# meuRelogio.net
KiCad netlist of a schematic drawn in EAGLE
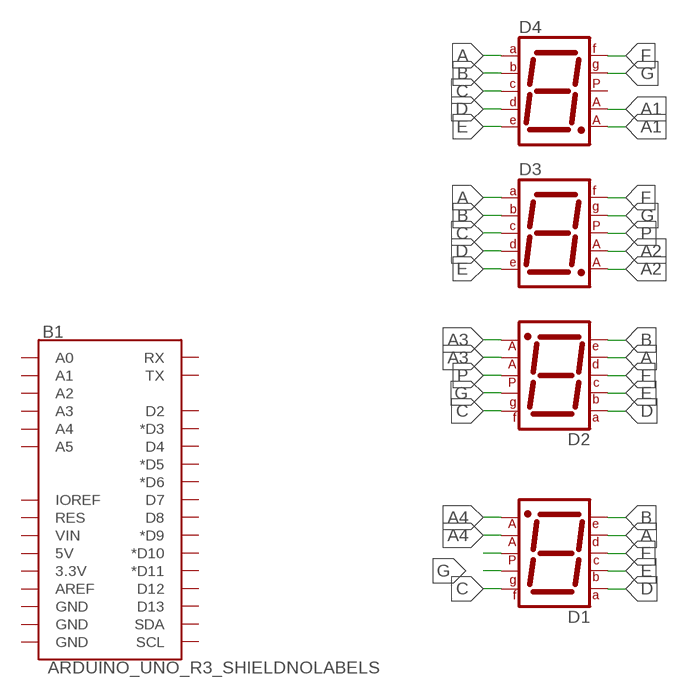
[diagram p0: schematic, sheet 1]

(export (version "E")
  (design (tool "Eeschema 10.0.6"))
  (components
    (comp (ref "B1")
      (value "ARDUINO_UNO_R3_SHIELDNOLABELS")
      (footprint "eagle-import:UNO_R3_SHIELD_NOLABELS")
      (libsource (lib "eagle-import") (part "ARDUINO_UNO_R3_SHIELDNOLABELS"))
    )
    (comp (ref "D1")
      (value "7SEG-CA")
      (footprint "eagle-import:7SEG-13")
      (libsource (lib "eagle-import") (part "7SEG-CA"))
    )
    (comp (ref "D2")
      (value "7SEG-CA")
      (footprint "eagle-import:7SEG-13")
      (libsource (lib "eagle-import") (part "7SEG-CA"))
    )
    (comp (ref "D3")
      (value "7SEG-CA")
      (footprint "eagle-import:7SEG-13")
      (libsource (lib "eagle-import") (part "7SEG-CA"))
    )
    (comp (ref "D4")
      (value "7SEG-CA")
      (footprint "eagle-import:7SEG-13")
      (libsource (lib "eagle-import") (part "7SEG-CA"))
    )
  )
  (nets
    (net (code "1") (name "A") (class "Default")
      (node (ref "D1") (pin "2") (pinfunction "D_2") (pintype "passive"))
      (node (ref "D2") (pin "2") (pinfunction "D_2") (pintype "passive"))
      (node (ref "D3") (pin "7") (pinfunction "A_7") (pintype "passive"))
      (node (ref "D4") (pin "7") (pinfunction "A_7") (pintype "passive"))
    )
    (net (code "2") (name "A1") (class "Default")
      (node (ref "D4") (pin "3") (pinfunction "CA1_3") (pintype "passive"))
      (node (ref "D4") (pin "8") (pinfunction "CA2_8") (pintype "passive"))
    )
    (net (code "3") (name "A2") (class "Default")
      (node (ref "D3") (pin "3") (pinfunction "CA1_3") (pintype "passive"))
      (node (ref "D3") (pin "8") (pinfunction "CA2_8") (pintype "passive"))
    )
    (net (code "4") (name "A3") (class "Default")
      (node (ref "D2") (pin "3") (pinfunction "CA1_3") (pintype "passive"))
      (node (ref "D2") (pin "8") (pinfunction "CA2_8") (pintype "passive"))
    )
    (net (code "5") (name "A4") (class "Default")
      (node (ref "D1") (pin "3") (pinfunction "CA1_3") (pintype "passive"))
      (node (ref "D1") (pin "8") (pinfunction "CA2_8") (pintype "passive"))
    )
    (net (code "6") (name "B") (class "Default")
      (node (ref "D1") (pin "1") (pinfunction "E_1") (pintype "passive"))
      (node (ref "D2") (pin "1") (pinfunction "E_1") (pintype "passive"))
      (node (ref "D3") (pin "6") (pinfunction "B_6") (pintype "passive"))
      (node (ref "D4") (pin "6") (pinfunction "B_6") (pintype "passive"))
    )
    (net (code "7") (name "C") (class "Default")
      (node (ref "D1") (pin "9") (pinfunction "F_9") (pintype "passive"))
      (node (ref "D2") (pin "9") (pinfunction "F_9") (pintype "passive"))
      (node (ref "D3") (pin "4") (pinfunction "C_4") (pintype "passive"))
      (node (ref "D4") (pin "4") (pinfunction "C_4") (pintype "passive"))
    )
    (net (code "8") (name "D") (class "Default")
      (node (ref "D1") (pin "7") (pinfunction "A_7") (pintype "passive"))
      (node (ref "D2") (pin "7") (pinfunction "A_7") (pintype "passive"))
      (node (ref "D3") (pin "2") (pinfunction "D_2") (pintype "passive"))
      (node (ref "D4") (pin "2") (pinfunction "D_2") (pintype "passive"))
    )
    (net (code "9") (name "E") (class "Default")
      (node (ref "D1") (pin "6") (pinfunction "B_6") (pintype "passive"))
      (node (ref "D2") (pin "6") (pinfunction "B_6") (pintype "passive"))
      (node (ref "D3") (pin "1") (pinfunction "E_1") (pintype "passive"))
      (node (ref "D4") (pin "1") (pinfunction "E_1") (pintype "passive"))
    )
    (net (code "10") (name "F") (class "Default")
      (node (ref "D1") (pin "4") (pinfunction "C_4") (pintype "passive"))
      (node (ref "D2") (pin "4") (pinfunction "C_4") (pintype "passive"))
      (node (ref "D3") (pin "9") (pinfunction "F_9") (pintype "passive"))
      (node (ref "D4") (pin "9") (pinfunction "F_9") (pintype "passive"))
    )
    (net (code "11") (name "G") (class "Default")
      (node (ref "D1") (pin "10") (pinfunction "G_10") (pintype "passive"))
      (node (ref "D2") (pin "10") (pinfunction "G_10") (pintype "passive"))
      (node (ref "D3") (pin "10") (pinfunction "G_10") (pintype "passive"))
      (node (ref "D4") (pin "10") (pinfunction "G_10") (pintype "passive"))
    )
    (net (code "12") (name "P") (class "Default")
      (node (ref "D2") (pin "5") (pinfunction "DP_5") (pintype "passive"))
      (node (ref "D3") (pin "5") (pinfunction "DP_5") (pintype "passive"))
    )
    (net (code "13") (name "unconnected-(B1-*D3-PadD3)") (class "Default")
      (node (ref "B1") (pin "D3") (pinfunction "*D3_D3") (pintype "bidirectional"))
    )
    (net (code "14") (name "unconnected-(B1-*D5-PadD5)") (class "Default")
      (node (ref "B1") (pin "D5") (pinfunction "*D5_D5") (pintype "bidirectional"))
    )
    (net (code "15") (name "unconnected-(B1-*D6-PadD6)") (class "Default")
      (node (ref "B1") (pin "D6") (pinfunction "*D6_D6") (pintype "bidirectional"))
    )
    (net (code "16") (name "unconnected-(B1-*D9-PadD9)") (class "Default")
      (node (ref "B1") (pin "D9") (pinfunction "*D9_D9") (pintype "bidirectional"))
    )
    (net (code "17") (name "unconnected-(B1-*D10-PadD10)") (class "Default")
      (node (ref "B1") (pin "D10") (pinfunction "*D10_D10") (pintype "bidirectional"))
    )
    (net (code "18") (name "unconnected-(B1-*D11-PadD11)") (class "Default")
      (node (ref "B1") (pin "D11") (pinfunction "*D11_D11") (pintype "bidirectional"))
    )
    (net (code "19") (name "unconnected-(B1-GND-PadGND@0)") (class "Default")
      (node (ref "B1") (pin "GND@0") (pinfunction "GND_GND@0") (pintype "bidirectional"))
    )
    (net (code "20") (name "unconnected-(B1-GND-PadGND@1)") (class "Default")
      (node (ref "B1") (pin "GND@1") (pinfunction "GND_GND@1") (pintype "bidirectional"))
    )
    (net (code "21") (name "unconnected-(B1-GND-PadGND@2)") (class "Default")
      (node (ref "B1") (pin "GND@2") (pinfunction "GND_GND@2") (pintype "bidirectional"))
    )
    (net (code "22") (name "unconnected-(B1-Pad3.3V)") (class "Default")
      (node (ref "B1") (pin "3.3V") (pinfunction "3.3V_3.3V") (pintype "bidirectional"))
    )
    (net (code "23") (name "unconnected-(B1-Pad5V)") (class "Default")
      (node (ref "B1") (pin "5V") (pinfunction "5V_5V") (pintype "bidirectional"))
    )
    (net (code "24") (name "unconnected-(B1-PadA0)") (class "Default")
      (node (ref "B1") (pin "A0") (pinfunction "A0_A0") (pintype "bidirectional"))
    )
    (net (code "25") (name "unconnected-(B1-PadA1)") (class "Default")
      (node (ref "B1") (pin "A1") (pinfunction "A1_A1") (pintype "bidirectional"))
    )
    (net (code "26") (name "unconnected-(B1-PadA2)") (class "Default")
      (node (ref "B1") (pin "A2") (pinfunction "A2_A2") (pintype "bidirectional"))
    )
    (net (code "27") (name "unconnected-(B1-PadA3)") (class "Default")
      (node (ref "B1") (pin "A3") (pinfunction "A3_A3") (pintype "bidirectional"))
    )
    (net (code "28") (name "unconnected-(B1-PadA4)") (class "Default")
      (node (ref "B1") (pin "A4") (pinfunction "A4_A4") (pintype "bidirectional"))
    )
    (net (code "29") (name "unconnected-(B1-PadA5)") (class "Default")
      (node (ref "B1") (pin "A5") (pinfunction "A5_A5") (pintype "bidirectional"))
    )
    (net (code "30") (name "unconnected-(B1-PadAREF)") (class "Default")
      (node (ref "B1") (pin "AREF") (pinfunction "AREF_AREF") (pintype "bidirectional"))
    )
    (net (code "31") (name "unconnected-(B1-PadD2)") (class "Default")
      (node (ref "B1") (pin "D2") (pinfunction "D2_D2") (pintype "bidirectional"))
    )
    (net (code "32") (name "unconnected-(B1-PadD4)") (class "Default")
      (node (ref "B1") (pin "D4") (pinfunction "D4_D4") (pintype "bidirectional"))
    )
    (net (code "33") (name "unconnected-(B1-PadD7)") (class "Default")
      (node (ref "B1") (pin "D7") (pinfunction "D7_D7") (pintype "bidirectional"))
    )
    (net (code "34") (name "unconnected-(B1-PadD8)") (class "Default")
      (node (ref "B1") (pin "D8") (pinfunction "D8_D8") (pintype "bidirectional"))
    )
    (net (code "35") (name "unconnected-(B1-PadD12)") (class "Default")
      (node (ref "B1") (pin "D12") (pinfunction "D12_D12") (pintype "bidirectional"))
    )
    (net (code "36") (name "unconnected-(B1-PadD13)") (class "Default")
      (node (ref "B1") (pin "D13") (pinfunction "D13_D13") (pintype "bidirectional"))
    )
    (net (code "37") (name "unconnected-(B1-PadIOREF)") (class "Default")
      (node (ref "B1") (pin "IOREF") (pinfunction "IOREF_IOREF") (pintype "bidirectional"))
    )
    (net (code "38") (name "unconnected-(B1-PadRES)") (class "Default")
      (node (ref "B1") (pin "RES") (pinfunction "RES_RES") (pintype "bidirectional"))
    )
    (net (code "39") (name "unconnected-(B1-PadRX)") (class "Default")
      (node (ref "B1") (pin "RX") (pinfunction "RX_RX") (pintype "bidirectional"))
    )
    (net (code "40") (name "unconnected-(B1-PadSCL)") (class "Default")
      (node (ref "B1") (pin "SCL") (pinfunction "SCL_SCL") (pintype "bidirectional"))
    )
    (net (code "41") (name "unconnected-(B1-PadSDA)") (class "Default")
      (node (ref "B1") (pin "SDA") (pinfunction "SDA_SDA") (pintype "bidirectional"))
    )
    (net (code "42") (name "unconnected-(B1-PadTX)") (class "Default")
      (node (ref "B1") (pin "TX") (pinfunction "TX_TX") (pintype "bidirectional"))
    )
    (net (code "43") (name "unconnected-(B1-PadVIN)") (class "Default")
      (node (ref "B1") (pin "VIN") (pinfunction "VIN_VIN") (pintype "bidirectional"))
    )
    (net (code "44") (name "unconnected-(D1-DP-Pad5)") (class "Default")
      (node (ref "D1") (pin "5") (pinfunction "DP_5") (pintype "passive"))
    )
    (net (code "45") (name "unconnected-(D4-DP-Pad5)") (class "Default")
      (node (ref "D4") (pin "5") (pinfunction "DP_5") (pintype "passive"))
    )
  )
)
